# lueur.net
KiCad netlist of a schematic drawn in EAGLE
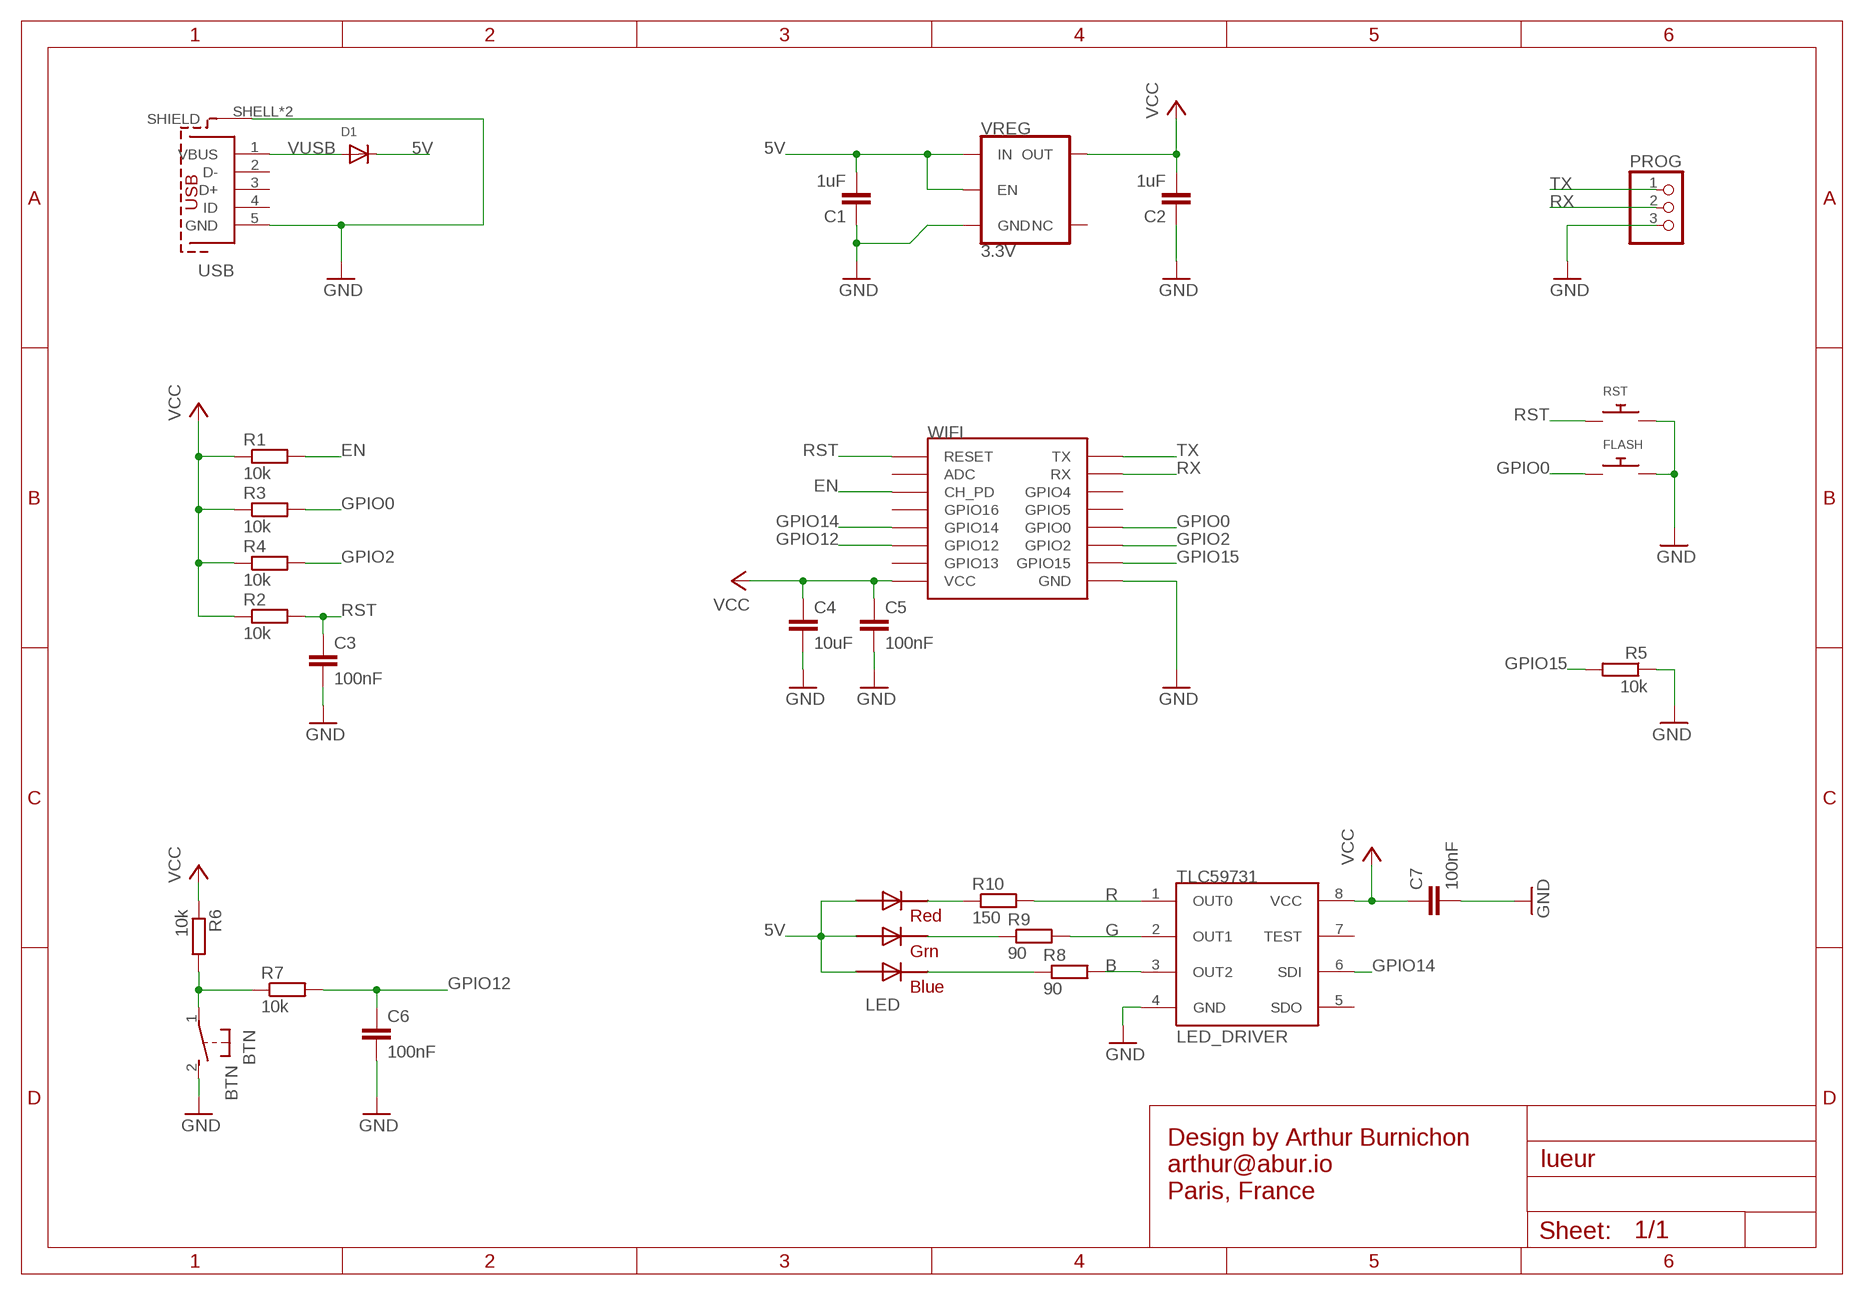
[diagram p0: schematic, sheet 1]

(export (version "E")
  (design (tool "Eeschema 10.0.6"))
  (components
    (comp (ref "BTN")
      (value "BTN")
      (footprint "eagle-import:B3F-31XX")
      (libsource (lib "eagle-import") (part "31-XX"))
    )
    (comp (ref "C1")
      (value "1uF")
      (footprint "eagle-import:C0805")
      (libsource (lib "eagle-import") (part "C-EUC0805"))
    )
    (comp (ref "C2")
      (value "1uF")
      (footprint "eagle-import:C0805")
      (libsource (lib "eagle-import") (part "C-EUC0805"))
    )
    (comp (ref "C3")
      (value "100nF")
      (footprint "eagle-import:C0805")
      (libsource (lib "eagle-import") (part "C-EUC0805"))
    )
    (comp (ref "C4")
      (value "10uF")
      (footprint "eagle-import:C0805")
      (libsource (lib "eagle-import") (part "C-EUC0805"))
    )
    (comp (ref "C5")
      (value "100nF")
      (footprint "eagle-import:C0805")
      (libsource (lib "eagle-import") (part "C-EUC0805"))
    )
    (comp (ref "C6")
      (value "100nF")
      (footprint "eagle-import:C0805")
      (libsource (lib "eagle-import") (part "C-EUC0805"))
    )
    (comp (ref "C7")
      (value "100nF")
      (footprint "eagle-import:C0805")
      (libsource (lib "eagle-import") (part "C-EUC0805"))
    )
    (comp (ref "D1")
      (value "DIODESMA")
      (footprint "eagle-import:SMADIODE")
      (libsource (lib "eagle-import") (part "DIODESMA"))
    )
    (comp (ref "FLASH")
      (value "SWITCH_PUSHBUTTONSOFTTOUCHSMD_SJ")
      (footprint "eagle-import:PUSHBUTTON_SMD_SJ")
      (libsource (lib "eagle-import") (part "SWITCH_PUSHBUTTONSOFTTOUCHSMD_SJ"))
    )
    (comp (ref "LED")
      (value "RGB5555")
      (footprint "eagle-import:RGBLED5050")
      (libsource (lib "eagle-import") (part "RGB5555"))
    )
    (comp (ref "LED_DRIVER")
      (value "TLC59731")
      (footprint "eagle-import:SOIC8")
      (libsource (lib "eagle-import") (part "TLC59731"))
    )
    (comp (ref "PROG")
      (value "PINHD-1X3")
      (footprint "eagle-import:1X03")
      (libsource (lib "eagle-import") (part "PINHD-1X3"))
    )
    (comp (ref "R1")
      (value "10k")
      (footprint "eagle-import:R0805")
      (libsource (lib "eagle-import") (part "R-EU_R0805"))
    )
    (comp (ref "R2")
      (value "10k")
      (footprint "eagle-import:R0805")
      (libsource (lib "eagle-import") (part "R-EU_R0805"))
    )
    (comp (ref "R3")
      (value "10k")
      (footprint "eagle-import:R0805")
      (libsource (lib "eagle-import") (part "R-EU_R0805"))
    )
    (comp (ref "R4")
      (value "10k")
      (footprint "eagle-import:R0805")
      (libsource (lib "eagle-import") (part "R-EU_R0805"))
    )
    (comp (ref "R5")
      (value "10k")
      (footprint "eagle-import:R0805")
      (libsource (lib "eagle-import") (part "R-EU_R0805"))
    )
    (comp (ref "R6")
      (value "10k")
      (footprint "eagle-import:R0805")
      (libsource (lib "eagle-import") (part "R-EU_R0805"))
    )
    (comp (ref "R7")
      (value "10k")
      (footprint "eagle-import:R0805")
      (libsource (lib "eagle-import") (part "R-EU_R0805"))
    )
    (comp (ref "R8")
      (value "90")
      (footprint "eagle-import:R0805")
      (libsource (lib "eagle-import") (part "R-EU_R0805"))
    )
    (comp (ref "R9")
      (value "90")
      (footprint "eagle-import:R0805")
      (libsource (lib "eagle-import") (part "R-EU_R0805"))
    )
    (comp (ref "R10")
      (value "150")
      (footprint "eagle-import:R0805")
      (libsource (lib "eagle-import") (part "R-EU_R0805"))
    )
    (comp (ref "RST")
      (value "SWITCH_PUSHBUTTONSOFTTOUCHSMD_SJ")
      (footprint "eagle-import:PUSHBUTTON_SMD_SJ")
      (libsource (lib "eagle-import") (part "SWITCH_PUSHBUTTONSOFTTOUCHSMD_SJ"))
    )
    (comp (ref "USB")
      (value "614105150721")
      (footprint "eagle-import:614105150721")
      (libsource (lib "eagle-import") (part "614105150721"))
    )
    (comp (ref "VREG")
      (value "3.3V")
      (footprint "eagle-import:SOT23-5")
      (libsource (lib "eagle-import") (part "V_REG_AP2112K-3.3V"))
    )
    (comp (ref "WIFI")
      (value "ESP12SMD")
      (footprint "eagle-import:ESP12-SMD")
      (libsource (lib "eagle-import") (part "ESP12SMD"))
    )
  )
  (nets
    (net (code "1") (name "/5V") (class "Default")
      (node (ref "C1") (pin "2") (pinfunction "2_2") (pintype "passive"))
      (node (ref "D1") (pin "C") (pinfunction "C_C") (pintype "passive"))
      (node (ref "LED") (pin "4") (pinfunction "RED_A_4") (pintype "bidirectional"))
      (node (ref "LED") (pin "5") (pinfunction "GREEN_A_5") (pintype "bidirectional"))
      (node (ref "LED") (pin "6") (pinfunction "BLUE_A_6") (pintype "bidirectional"))
      (node (ref "VREG") (pin "1") (pinfunction "IN_1") (pintype "input"))
      (node (ref "VREG") (pin "3") (pinfunction "EN_3") (pintype "input"))
    )
    (net (code "2") (name "/B") (class "Default")
      (node (ref "LED_DRIVER") (pin "3") (pinfunction "OUT2_3") (pintype "bidirectional"))
      (node (ref "R8") (pin "2") (pinfunction "2_2") (pintype "passive"))
    )
    (net (code "3") (name "/EN") (class "Default")
      (node (ref "R1") (pin "2") (pinfunction "2_2") (pintype "passive"))
      (node (ref "WIFI") (pin "CH_PD") (pinfunction "CH_PD_CH_PD") (pintype "bidirectional"))
    )
    (net (code "4") (name "/G") (class "Default")
      (node (ref "LED_DRIVER") (pin "2") (pinfunction "OUT1_2") (pintype "bidirectional"))
      (node (ref "R9") (pin "2") (pinfunction "2_2") (pintype "passive"))
    )
    (net (code "5") (name "/GPIO0") (class "Default")
      (node (ref "FLASH") (pin "P$1") (pinfunction "P$1_P$1") (pintype "passive"))
      (node (ref "R3") (pin "2") (pinfunction "2_2") (pintype "passive"))
      (node (ref "WIFI") (pin "GPIO0") (pinfunction "GPIO0_GPIO0") (pintype "bidirectional"))
    )
    (net (code "6") (name "/GPIO2") (class "Default")
      (node (ref "R4") (pin "2") (pinfunction "2_2") (pintype "passive"))
      (node (ref "WIFI") (pin "GPIO2") (pinfunction "GPIO2_GPIO2") (pintype "bidirectional"))
    )
    (net (code "7") (name "/GPIO12") (class "Default")
      (node (ref "C6") (pin "1") (pinfunction "1_1") (pintype "passive"))
      (node (ref "R7") (pin "2") (pinfunction "2_2") (pintype "passive"))
      (node (ref "WIFI") (pin "GPIO12") (pinfunction "GPIO12_GPIO12") (pintype "bidirectional"))
    )
    (net (code "8") (name "/GPIO14") (class "Default")
      (node (ref "LED_DRIVER") (pin "6") (pinfunction "SDI_6") (pintype "bidirectional"))
      (node (ref "WIFI") (pin "GPIO14") (pinfunction "GPIO14_GPIO14") (pintype "bidirectional"))
    )
    (net (code "9") (name "/GPIO15") (class "Default")
      (node (ref "R5") (pin "2") (pinfunction "2_2") (pintype "passive"))
      (node (ref "WIFI") (pin "GPIO15") (pinfunction "GPIO15_GPIO15") (pintype "bidirectional"))
    )
    (net (code "10") (name "/R") (class "Default")
      (node (ref "LED_DRIVER") (pin "1") (pinfunction "OUT0_1") (pintype "bidirectional"))
      (node (ref "R10") (pin "2") (pinfunction "2_2") (pintype "passive"))
    )
    (net (code "11") (name "/RST") (class "Default")
      (node (ref "C3") (pin "1") (pinfunction "1_1") (pintype "passive"))
      (node (ref "R2") (pin "2") (pinfunction "2_2") (pintype "passive"))
      (node (ref "RST") (pin "P$1") (pinfunction "P$1_P$1") (pintype "passive"))
      (node (ref "WIFI") (pin "RESET") (pinfunction "RESET_RESET") (pintype "bidirectional"))
    )
    (net (code "12") (name "/RX") (class "Default")
      (node (ref "PROG") (pin "2") (pinfunction "2_2") (pintype "passive"))
      (node (ref "WIFI") (pin "RXD0") (pinfunction "RX_RXD0") (pintype "bidirectional"))
    )
    (net (code "13") (name "/TX") (class "Default")
      (node (ref "PROG") (pin "1") (pinfunction "1_1") (pintype "passive"))
      (node (ref "WIFI") (pin "TXD0") (pinfunction "TX_TXD0") (pintype "bidirectional"))
    )
    (net (code "14") (name "/VUSB") (class "Default")
      (node (ref "D1") (pin "A") (pinfunction "A_A") (pintype "passive"))
      (node (ref "USB") (pin "1") (pinfunction "VBUS_1") (pintype "passive"))
    )
    (net (code "15") (name "GND") (class "Default")
      (node (ref "BTN") (pin "2") (pinfunction "S_2") (pintype "passive"))
      (node (ref "C1") (pin "1") (pinfunction "1_1") (pintype "passive"))
      (node (ref "C2") (pin "1") (pinfunction "1_1") (pintype "passive"))
      (node (ref "C3") (pin "2") (pinfunction "2_2") (pintype "passive"))
      (node (ref "C4") (pin "2") (pinfunction "2_2") (pintype "passive"))
      (node (ref "C5") (pin "2") (pinfunction "2_2") (pintype "passive"))
      (node (ref "C6") (pin "2") (pinfunction "2_2") (pintype "passive"))
      (node (ref "C7") (pin "2") (pinfunction "2_2") (pintype "passive"))
      (node (ref "FLASH") (pin "P$2") (pinfunction "P$2_P$2") (pintype "passive"))
      (node (ref "LED_DRIVER") (pin "4") (pinfunction "GND_4") (pintype "bidirectional"))
      (node (ref "PROG") (pin "3") (pinfunction "3_3") (pintype "passive"))
      (node (ref "R5") (pin "1") (pinfunction "1_1") (pintype "passive"))
      (node (ref "RST") (pin "P$2") (pinfunction "P$2_P$2") (pintype "passive"))
      (node (ref "USB") (pin "5") (pinfunction "GND_5") (pintype "passive"))
      (node (ref "USB") (pin "SHELL") (pinfunction "SHIELD_SHELL") (pintype "passive"))
      (node (ref "USB") (pin "SHELL1") (pinfunction "SHIELD_SHELL1") (pintype "passive"))
      (node (ref "VREG") (pin "2") (pinfunction "GND_2") (pintype "input"))
      (node (ref "WIFI") (pin "GND") (pinfunction "GND_GND") (pintype "bidirectional"))
    )
    (net (code "16") (name "Net-(BTN-P)") (class "Default")
      (node (ref "BTN") (pin "1") (pinfunction "P_1") (pintype "passive"))
      (node (ref "R6") (pin "2") (pinfunction "2_2") (pintype "passive"))
      (node (ref "R7") (pin "1") (pinfunction "1_1") (pintype "passive"))
    )
    (net (code "17") (name "Net-(LED-BLUE_C)") (class "Default")
      (node (ref "LED") (pin "1") (pinfunction "BLUE_C_1") (pintype "bidirectional"))
      (node (ref "R8") (pin "1") (pinfunction "1_1") (pintype "passive"))
    )
    (net (code "18") (name "Net-(LED-GREEN_C)") (class "Default")
      (node (ref "LED") (pin "2") (pinfunction "GREEN_C_2") (pintype "bidirectional"))
      (node (ref "R9") (pin "1") (pinfunction "1_1") (pintype "passive"))
    )
    (net (code "19") (name "Net-(LED-RED_C)") (class "Default")
      (node (ref "LED") (pin "3") (pinfunction "RED_C_3") (pintype "bidirectional"))
      (node (ref "R10") (pin "1") (pinfunction "1_1") (pintype "passive"))
    )
    (net (code "20") (name "VCC") (class "Default")
      (node (ref "C2") (pin "2") (pinfunction "2_2") (pintype "passive"))
      (node (ref "C4") (pin "1") (pinfunction "1_1") (pintype "passive"))
      (node (ref "C5") (pin "1") (pinfunction "1_1") (pintype "passive"))
      (node (ref "C7") (pin "1") (pinfunction "1_1") (pintype "passive"))
      (node (ref "LED_DRIVER") (pin "8") (pinfunction "VCC_8") (pintype "bidirectional"))
      (node (ref "R1") (pin "1") (pinfunction "1_1") (pintype "passive"))
      (node (ref "R2") (pin "1") (pinfunction "1_1") (pintype "passive"))
      (node (ref "R3") (pin "1") (pinfunction "1_1") (pintype "passive"))
      (node (ref "R4") (pin "1") (pinfunction "1_1") (pintype "passive"))
      (node (ref "R6") (pin "1") (pinfunction "1_1") (pintype "passive"))
      (node (ref "VREG") (pin "5") (pinfunction "OUT_5") (pintype "passive"))
      (node (ref "WIFI") (pin "VCC") (pinfunction "VCC_VCC") (pintype "bidirectional"))
    )
    (net (code "21") (name "unconnected-(LED_DRIVER-SDO-Pad5)") (class "Default")
      (node (ref "LED_DRIVER") (pin "5") (pinfunction "SDO_5") (pintype "bidirectional"))
    )
    (net (code "22") (name "unconnected-(LED_DRIVER-TEST-Pad7)") (class "Default")
      (node (ref "LED_DRIVER") (pin "7") (pinfunction "TEST_7") (pintype "bidirectional"))
    )
    (net (code "23") (name "unconnected-(USB-D+-Pad3)") (class "Default")
      (node (ref "USB") (pin "3") (pinfunction "D+_3") (pintype "passive"))
    )
    (net (code "24") (name "unconnected-(USB-D--Pad2)") (class "Default")
      (node (ref "USB") (pin "2") (pinfunction "D-_2") (pintype "passive"))
    )
    (net (code "25") (name "unconnected-(USB-ID-Pad4)") (class "Default")
      (node (ref "USB") (pin "4") (pinfunction "ID_4") (pintype "passive"))
    )
    (net (code "26") (name "unconnected-(VREG-NC-Pad4)") (class "Default")
      (node (ref "VREG") (pin "4") (pinfunction "NC_4") (pintype "no_connect"))
    )
    (net (code "27") (name "unconnected-(WIFI-PadADC)") (class "Default")
      (node (ref "WIFI") (pin "ADC") (pinfunction "ADC_ADC") (pintype "bidirectional"))
    )
    (net (code "28") (name "unconnected-(WIFI-PadGPIO4)") (class "Default")
      (node (ref "WIFI") (pin "GPIO4") (pinfunction "GPIO4_GPIO4") (pintype "bidirectional"))
    )
    (net (code "29") (name "unconnected-(WIFI-PadGPIO5)") (class "Default")
      (node (ref "WIFI") (pin "GPIO5") (pinfunction "GPIO5_GPIO5") (pintype "bidirectional"))
    )
    (net (code "30") (name "unconnected-(WIFI-PadGPIO13)") (class "Default")
      (node (ref "WIFI") (pin "GPIO13") (pinfunction "GPIO13_GPIO13") (pintype "bidirectional"))
    )
    (net (code "31") (name "unconnected-(WIFI-PadGPIO16)") (class "Default")
      (node (ref "WIFI") (pin "GPIO16") (pinfunction "GPIO16_GPIO16") (pintype "bidirectional"))
    )
  )
)
